# in3temperature.net
KiCad netlist of a schematic drawn in EAGLE
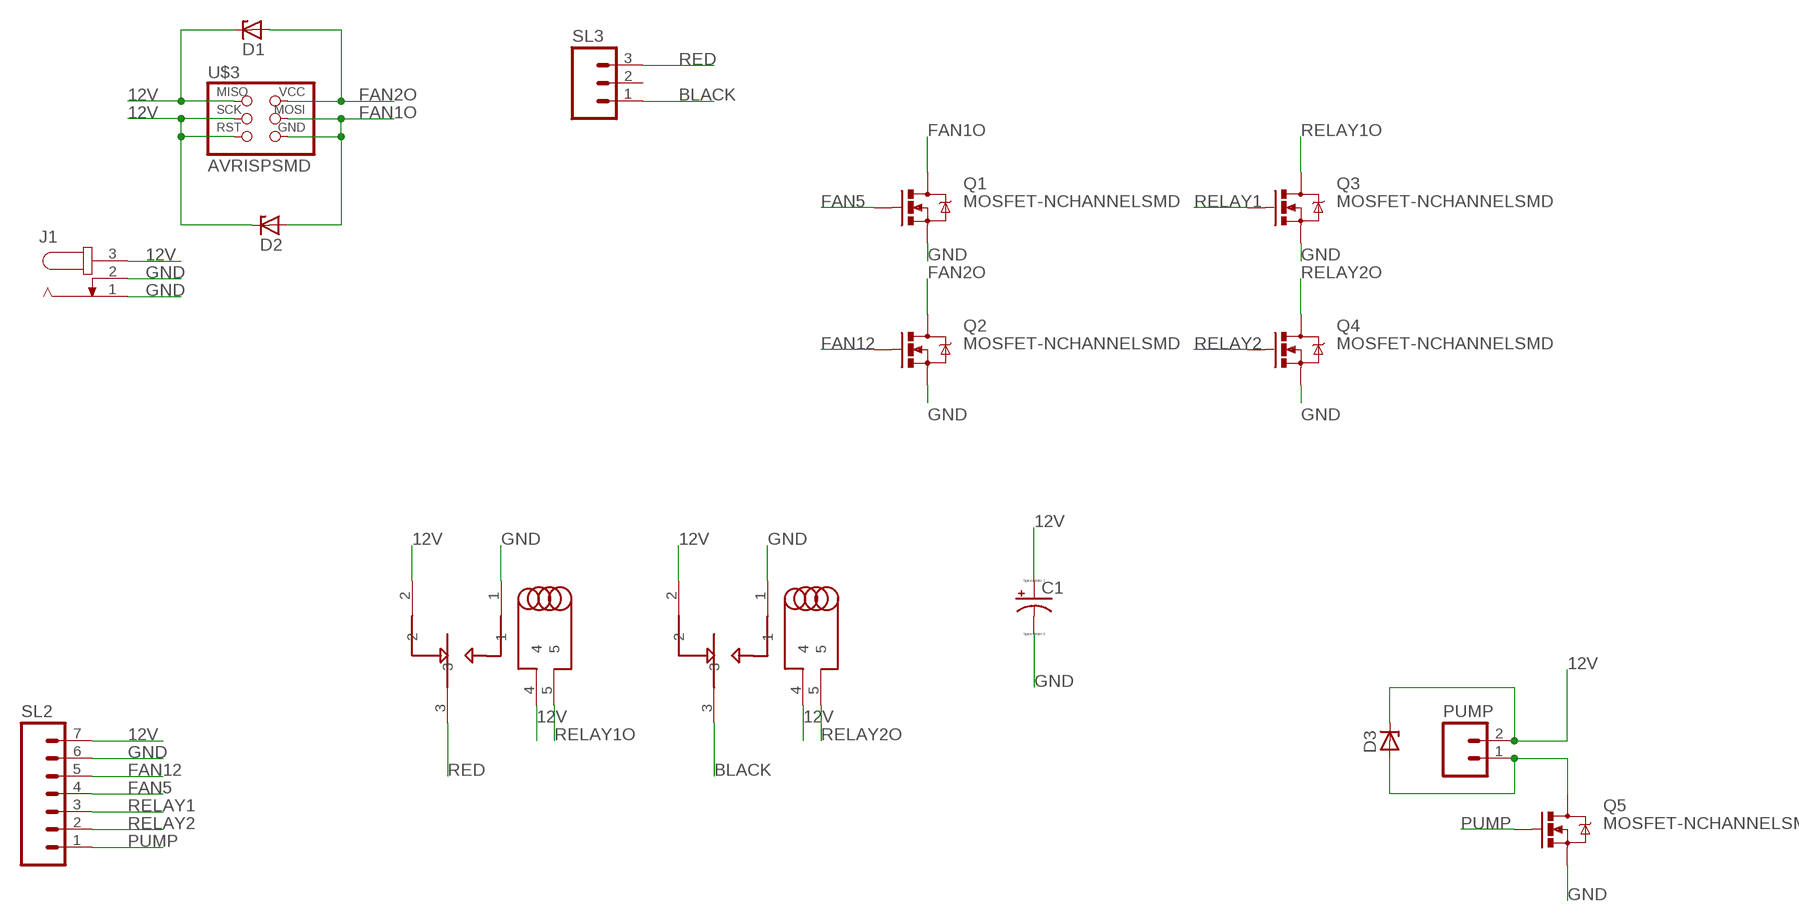
[diagram p0: schematic, sheet 1]

(export (version "E")
  (design (tool "Eeschema 10.0.6"))
  (components
    (comp (ref "C1")
      (value "CPOL-USE2.5-5")
      (footprint "eagle-import:E2,5-5")
      (libsource (lib "eagle-import") (part "CPOL-USE2.5-5"))
    )
    (comp (ref "D1")
      (value "ZENER_DIODESOD123")
      (footprint "eagle-import:SOD123")
      (libsource (lib "eagle-import") (part "ZENER_DIODESOD123"))
    )
    (comp (ref "D2")
      (value "ZENER_DIODESOD123")
      (footprint "eagle-import:SOD123")
      (libsource (lib "eagle-import") (part "ZENER_DIODESOD123"))
    )
    (comp (ref "D3")
      (value "ZENER_DIODESOD123")
      (footprint "eagle-import:SOD123")
      (libsource (lib "eagle-import") (part "ZENER_DIODESOD123"))
    )
    (comp (ref "J1")
      (value "JACK-PLUG1")
      (footprint "eagle-import:SPC4078")
      (libsource (lib "eagle-import") (part "JACK-PLUG1"))
    )
    (comp (ref "PUMP")
      (value "MA02")
      (footprint "eagle-import:02PA")
      (libsource (lib "eagle-import") (part "MA02"))
    )
    (comp (ref "Q1")
      (value "MOSFET-NCHANNELSMD")
      (footprint "eagle-import:SOT23-3")
      (libsource (lib "eagle-import") (part "MOSFET-NCHANNELSMD"))
    )
    (comp (ref "Q2")
      (value "MOSFET-NCHANNELSMD")
      (footprint "eagle-import:SOT23-3")
      (libsource (lib "eagle-import") (part "MOSFET-NCHANNELSMD"))
    )
    (comp (ref "Q3")
      (value "MOSFET-NCHANNELSMD")
      (footprint "eagle-import:SOT23-3")
      (libsource (lib "eagle-import") (part "MOSFET-NCHANNELSMD"))
    )
    (comp (ref "Q4")
      (value "MOSFET-NCHANNELSMD")
      (footprint "eagle-import:SOT23-3")
      (libsource (lib "eagle-import") (part "MOSFET-NCHANNELSMD"))
    )
    (comp (ref "Q5")
      (value "MOSFET-NCHANNELSMD")
      (footprint "eagle-import:SOT23-3")
      (libsource (lib "eagle-import") (part "MOSFET-NCHANNELSMD"))
    )
    (comp (ref "SL2")
      (value "MA07")
      (footprint "eagle-import:07PA")
      (libsource (lib "eagle-import") (part "MA07"))
    )
    (comp (ref "SL3")
      (value "MA03")
      (footprint "eagle-import:03P")
      (libsource (lib "eagle-import") (part "MA03"))
    )
    (comp (ref "U$1")
      (value "RELAY-V23092THROUGH_HOLE")
      (footprint "eagle-import:RELAY-V23092")
      (libsource (lib "eagle-import") (part "RELAY-V23092THROUGH_HOLE"))
    )
    (comp (ref "U$2")
      (value "RELAY-V23092THROUGH_HOLE")
      (footprint "eagle-import:RELAY-V23092")
      (libsource (lib "eagle-import") (part "RELAY-V23092THROUGH_HOLE"))
    )
    (comp (ref "U$3")
      (value "AVRISPSMD")
      (footprint "eagle-import:2X03SMD")
      (libsource (lib "eagle-import") (part "AVRISPSMD"))
    )
  )
  (nets
    (net (code "1") (name "/12V") (class "Default")
      (node (ref "C1") (pin "+") (pinfunction "+_+") (pintype "passive"))
      (node (ref "D1") (pin "CATHODE") (pinfunction "CATHODE_CATHODE") (pintype "passive"))
      (node (ref "D2") (pin "CATHODE") (pinfunction "CATHODE_CATHODE") (pintype "passive"))
      (node (ref "D3") (pin "CATHODE") (pinfunction "CATHODE_CATHODE") (pintype "passive"))
      (node (ref "J1") (pin "3") (pinfunction "3_3") (pintype "passive"))
      (node (ref "PUMP") (pin "2") (pinfunction "2_2") (pintype "passive"))
      (node (ref "SL2") (pin "7") (pinfunction "7_7") (pintype "passive"))
      (node (ref "U$1") (pin "2") (pinfunction "2_2") (pintype "bidirectional"))
      (node (ref "U$1") (pin "4") (pinfunction "4_4") (pintype "bidirectional"))
      (node (ref "U$2") (pin "2") (pinfunction "2_2") (pintype "bidirectional"))
      (node (ref "U$2") (pin "4") (pinfunction "4_4") (pintype "bidirectional"))
      (node (ref "U$3") (pin "1") (pinfunction "MISO_1") (pintype "passive"))
      (node (ref "U$3") (pin "3") (pinfunction "SCK_3") (pintype "passive"))
      (node (ref "U$3") (pin "5") (pinfunction "RST_5") (pintype "passive"))
    )
    (net (code "2") (name "/BLACK") (class "Default")
      (node (ref "SL3") (pin "1") (pinfunction "1_1") (pintype "passive"))
      (node (ref "U$2") (pin "3") (pinfunction "3_3") (pintype "bidirectional"))
    )
    (net (code "3") (name "/FAN1O") (class "Default")
      (node (ref "D2") (pin "ANODE") (pinfunction "ANODE_ANODE") (pintype "passive"))
      (node (ref "Q1") (pin "3") (pinfunction "D_3") (pintype "passive"))
      (node (ref "U$3") (pin "4") (pinfunction "MOSI_4") (pintype "passive"))
      (node (ref "U$3") (pin "6") (pinfunction "GND_6") (pintype "passive"))
    )
    (net (code "4") (name "/FAN2O") (class "Default")
      (node (ref "D1") (pin "ANODE") (pinfunction "ANODE_ANODE") (pintype "passive"))
      (node (ref "Q2") (pin "3") (pinfunction "D_3") (pintype "passive"))
      (node (ref "U$3") (pin "2") (pinfunction "VCC_2") (pintype "passive"))
    )
    (net (code "5") (name "/FAN5") (class "Default")
      (node (ref "Q1") (pin "1") (pinfunction "G_1") (pintype "passive"))
      (node (ref "SL2") (pin "4") (pinfunction "4_4") (pintype "passive"))
    )
    (net (code "6") (name "/FAN12") (class "Default")
      (node (ref "Q2") (pin "1") (pinfunction "G_1") (pintype "passive"))
      (node (ref "SL2") (pin "5") (pinfunction "5_5") (pintype "passive"))
    )
    (net (code "7") (name "/GND") (class "Default")
      (node (ref "C1") (pin "-") (pinfunction "-_-") (pintype "passive"))
      (node (ref "J1") (pin "1") (pinfunction "1_1") (pintype "passive"))
      (node (ref "J1") (pin "2") (pinfunction "2_2") (pintype "passive"))
      (node (ref "Q1") (pin "2") (pinfunction "S_2") (pintype "passive"))
      (node (ref "Q2") (pin "2") (pinfunction "S_2") (pintype "passive"))
      (node (ref "Q3") (pin "2") (pinfunction "S_2") (pintype "passive"))
      (node (ref "Q4") (pin "2") (pinfunction "S_2") (pintype "passive"))
      (node (ref "Q5") (pin "2") (pinfunction "S_2") (pintype "passive"))
      (node (ref "SL2") (pin "6") (pinfunction "6_6") (pintype "passive"))
      (node (ref "U$1") (pin "1") (pinfunction "1_1") (pintype "bidirectional"))
      (node (ref "U$2") (pin "1") (pinfunction "1_1") (pintype "bidirectional"))
    )
    (net (code "8") (name "/PUMP") (class "Default")
      (node (ref "Q5") (pin "1") (pinfunction "G_1") (pintype "passive"))
      (node (ref "SL2") (pin "1") (pinfunction "1_1") (pintype "passive"))
    )
    (net (code "9") (name "/RED") (class "Default")
      (node (ref "SL3") (pin "3") (pinfunction "3_3") (pintype "passive"))
      (node (ref "U$1") (pin "3") (pinfunction "3_3") (pintype "bidirectional"))
    )
    (net (code "10") (name "/RELAY1") (class "Default")
      (node (ref "Q3") (pin "1") (pinfunction "G_1") (pintype "passive"))
      (node (ref "SL2") (pin "3") (pinfunction "3_3") (pintype "passive"))
    )
    (net (code "11") (name "/RELAY1O") (class "Default")
      (node (ref "Q3") (pin "3") (pinfunction "D_3") (pintype "passive"))
      (node (ref "U$1") (pin "5") (pinfunction "5_5") (pintype "bidirectional"))
    )
    (net (code "12") (name "/RELAY2") (class "Default")
      (node (ref "Q4") (pin "1") (pinfunction "G_1") (pintype "passive"))
      (node (ref "SL2") (pin "2") (pinfunction "2_2") (pintype "passive"))
    )
    (net (code "13") (name "/RELAY2O") (class "Default")
      (node (ref "Q4") (pin "3") (pinfunction "D_3") (pintype "passive"))
      (node (ref "U$2") (pin "5") (pinfunction "5_5") (pintype "bidirectional"))
    )
    (net (code "14") (name "Net-(Q5-D)") (class "Default")
      (node (ref "D3") (pin "ANODE") (pinfunction "ANODE_ANODE") (pintype "passive"))
      (node (ref "PUMP") (pin "1") (pinfunction "1_1") (pintype "passive"))
      (node (ref "Q5") (pin "3") (pinfunction "D_3") (pintype "passive"))
    )
    (net (code "15") (name "unconnected-(SL3-Pad2)") (class "Default")
      (node (ref "SL3") (pin "2") (pinfunction "2_2") (pintype "passive"))
    )
  )
)
